# Transformer_FrontEnd_3.net
KiCad netlist of a schematic drawn in Altium Designer
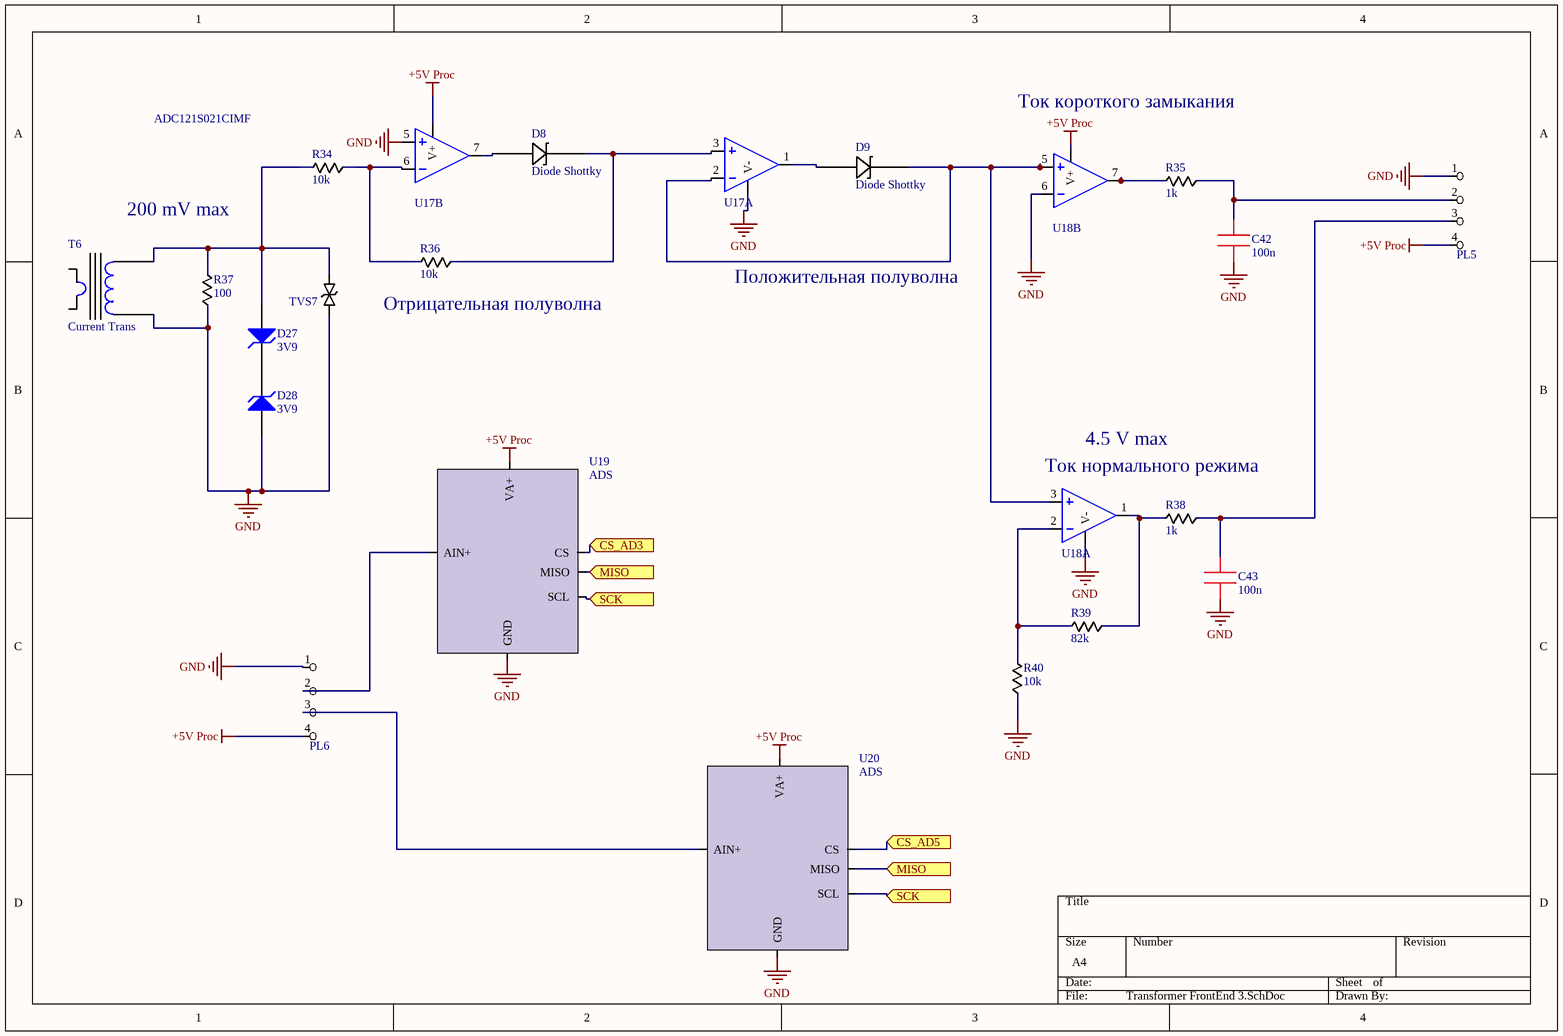
[diagram p0: Transformer FrontEnd 3.SchDoc]

(export (version "E")
  (design (tool "Eeschema 10.0.6"))
  (components
    (comp (ref "C42")
      (value "100n")
      (footprint "0603")
      (description "CC0603KRX7R9BB104")
      (libsource (lib "kontr") (part "0603 CAP"))
    )
    (comp (ref "C43")
      (value "100n")
      (footprint "0603")
      (description "CC0603KRX7R9BB104")
      (libsource (lib "kontr") (part "0603 CAP"))
    )
    (comp (ref "D8")
      (value "Diode Shottky")
      (footprint "SOD523")
      (description "RB751S40T1G")
      (libsource (lib "kontr") (part "Diode Shottky"))
    )
    (comp (ref "D9")
      (value "Diode Shottky")
      (footprint "SOD523")
      (description "RB751S40T1G")
      (libsource (lib "kontr") (part "Diode Shottky"))
    )
    (comp (ref "D27")
      (value "3V9")
      (footprint "PcbLib1:SOD80C")
      (description "BZV55-C3V9,115")
      (libsource (lib "Miscellaneous Devices") (part "D Zener"))
    )
    (comp (ref "D28")
      (value "3V9")
      (footprint "PcbLib1:SOD80C")
      (description "BZV55-C3V9,115")
      (libsource (lib "Miscellaneous Devices") (part "D Zener"))
    )
    (comp (ref "PL5")
      (value "plug")
      (footprint "PLS 4")
      (description "PLS-4R (DS1022-1x4R)")
      (libsource (lib "kontr") (part "PLS-4R"))
    )
    (comp (ref "PL6")
      (value "plug")
      (footprint "PLS 4")
      (description "PLS-4R (DS1022-1x4R)")
      (libsource (lib "kontr") (part "PLS-4R"))
    )
    (comp (ref "R34")
      (value "10k")
      (footprint "0603")
      (description "RT0603FRE0710KL")
      (libsource (lib "kontr") (part "0603 RES"))
    )
    (comp (ref "R35")
      (value "1k")
      (footprint "0603")
      (description "RC0603FR-071KL")
      (libsource (lib "kontr") (part "0603 RES"))
    )
    (comp (ref "R36")
      (value "10k")
      (footprint "0603")
      (description "RT0603FRE0710KL")
      (libsource (lib "kontr") (part "0603 RES"))
    )
    (comp (ref "R37")
      (value "100")
      (footprint "1206")
      (description "RT1206BRD07100RL")
      (libsource (lib "kontr") (part "SMD Resistor"))
    )
    (comp (ref "R38")
      (value "1k")
      (footprint "0603")
      (description "RC0603FR-071KL")
      (libsource (lib "kontr") (part "0603 RES"))
    )
    (comp (ref "R39")
      (value "82k")
      (footprint "0603")
      (description "ERJ3EKF8202V")
      (libsource (lib "kontr") (part "0603 RES"))
    )
    (comp (ref "R40")
      (value "10k")
      (footprint "0603")
      (description "RT0603FRE0710KL")
      (libsource (lib "kontr") (part "0603 RES"))
    )
    (comp (ref "T6")
      (value "Current Trans")
      (footprint "Talema")
      (description "AC-1005")
      (libsource (lib "kontr") (part "Current Trans"))
    )
    (comp (ref "TVS7")
      (value "SMAJ5.0CA")
      (footprint "DO-214AC")
      (libsource (lib "kontr") (part "SMAJ5.0CA"))
    )
    (comp (ref "U17")
      (value "OPAMP 2Ch")
      (footprint "SOIC 8")
      (description "TS272IDT")
      (libsource (lib "kontr") (part "OPAMP 2Ch"))
    )
    (comp (ref "U18")
      (value "OPAMP 2Ch")
      (footprint "SOIC 8")
      (description "TS272IDT")
      (libsource (lib "kontr") (part "OPAMP 2Ch"))
    )
    (comp (ref "U19")
      (value "ADS")
      (footprint "SOT23 - 6")
      (description "ADC121S021CIMF")
      (libsource (lib "kontr") (part "ADS"))
    )
    (comp (ref "U20")
      (value "ADS")
      (footprint "SOT23 - 6")
      (description "ADC121S021CIMF")
      (libsource (lib "kontr") (part "ADS"))
    )
  )
  (nets
    (net (code "1") (name "+5V Proc") (class "Default")
      (node (ref "PL5") (pin "4") (pinfunction "2_4") (pintype "passive"))
      (node (ref "PL6") (pin "4") (pinfunction "2_4") (pintype "passive"))
      (node (ref "U17") (pin "8") (pinfunction "V+_8") (pintype "passive"))
      (node (ref "U18") (pin "8") (pinfunction "V+_8") (pintype "passive"))
      (node (ref "U19") (pin "1") (pinfunction "VA+_1") (pintype "passive"))
      (node (ref "U20") (pin "1") (pinfunction "VA+_1") (pintype "passive"))
    )
    (net (code "2") (name "/CS_AD3") (class "Default")
      (node (ref "U19") (pin "6") (pinfunction "CS_6") (pintype "passive"))
    )
    (net (code "3") (name "/CS_AD5") (class "Default")
      (node (ref "U20") (pin "6") (pinfunction "CS_6") (pintype "passive"))
    )
    (net (code "4") (name "/MISO") (class "Default")
      (node (ref "U19") (pin "5") (pinfunction "MISO_5") (pintype "passive"))
      (node (ref "U20") (pin "5") (pinfunction "MISO_5") (pintype "passive"))
    )
    (net (code "5") (name "/SCK") (class "Default")
      (node (ref "U19") (pin "4") (pinfunction "SCL_4") (pintype "passive"))
      (node (ref "U20") (pin "4") (pinfunction "SCL_4") (pintype "passive"))
    )
    (net (code "6") (name "GND") (class "Default")
      (node (ref "C42") (pin "1") (pinfunction "1_1") (pintype "passive"))
      (node (ref "C43") (pin "1") (pinfunction "1_1") (pintype "passive"))
      (node (ref "D28") (pin "1") (pinfunction "A_1") (pintype "passive"))
      (node (ref "PL5") (pin "1") (pinfunction "1_1") (pintype "passive"))
      (node (ref "PL6") (pin "1") (pinfunction "1_1") (pintype "passive"))
      (node (ref "R37") (pin "1") (pintype "passive"))
      (node (ref "R40") (pin "1") (pintype "passive"))
      (node (ref "T6") (pin "2") (pinfunction "2_2") (pintype "passive"))
      (node (ref "TVS7") (pin "1") (pinfunction "1_1") (pintype "passive"))
      (node (ref "U17") (pin "4") (pinfunction "V-_4") (pintype "passive"))
      (node (ref "U17") (pin "5") (pinfunction "+IN_5") (pintype "passive"))
      (node (ref "U18") (pin "4") (pinfunction "V-_4") (pintype "passive"))
      (node (ref "U18") (pin "6") (pinfunction "-IN_6") (pintype "passive"))
      (node (ref "U19") (pin "2") (pinfunction "GND_2") (pintype "passive"))
      (node (ref "U20") (pin "2") (pinfunction "GND_2") (pintype "passive"))
    )
    (net (code "7") (name "Net-(C42-Pad2)") (class "Default")
      (node (ref "C42") (pin "2") (pinfunction "2_2") (pintype "passive"))
      (node (ref "PL5") (pin "2") (pinfunction "2_2") (pintype "passive"))
      (node (ref "R35") (pin "1") (pintype "passive"))
    )
    (net (code "8") (name "Net-(C43-Pad2)") (class "Default")
      (node (ref "C43") (pin "2") (pinfunction "2_2") (pintype "passive"))
      (node (ref "PL5") (pin "3") (pinfunction "1_3") (pintype "passive"))
      (node (ref "R38") (pin "1") (pintype "passive"))
    )
    (net (code "9") (name "Net-(D27-A)") (class "Default")
      (node (ref "D27") (pin "1") (pinfunction "A_1") (pintype "passive"))
      (node (ref "R34") (pin "2") (pintype "passive"))
      (node (ref "R37") (pin "2") (pintype "passive"))
      (node (ref "T6") (pin "1") (pinfunction "1_1") (pintype "passive"))
      (node (ref "TVS7") (pin "2") (pinfunction "2_2") (pintype "passive"))
    )
    (net (code "10") (name "Net-(D27-K)") (class "Default")
      (node (ref "D27") (pin "2") (pinfunction "K_2") (pintype "passive"))
      (node (ref "D28") (pin "2") (pinfunction "K_2") (pintype "passive"))
    )
    (net (code "11") (name "Net-(U17A-+IN)") (class "Default")
      (node (ref "D8") (pin "2") (pinfunction "2_2") (pintype "passive"))
      (node (ref "R36") (pin "1") (pintype "passive"))
      (node (ref "U17") (pin "3") (pinfunction "+IN_3") (pintype "passive"))
    )
    (net (code "12") (name "Net-(U17A--IN)") (class "Default")
      (node (ref "D9") (pin "2") (pinfunction "2_2") (pintype "passive"))
      (node (ref "U17") (pin "2") (pinfunction "-IN_2") (pintype "passive"))
      (node (ref "U18") (pin "3") (pinfunction "+IN_3") (pintype "passive"))
      (node (ref "U18") (pin "5") (pinfunction "+IN_5") (pintype "passive"))
    )
    (net (code "13") (name "Net-(U17A-OUT)") (class "Default")
      (node (ref "D9") (pin "1") (pinfunction "1_1") (pintype "passive"))
      (node (ref "U17") (pin "1") (pinfunction "OUT_1") (pintype "passive"))
    )
    (net (code "14") (name "Net-(U17B--IN)") (class "Default")
      (node (ref "R34") (pin "1") (pintype "passive"))
      (node (ref "R36") (pin "2") (pintype "passive"))
      (node (ref "U17") (pin "6") (pinfunction "-IN_6") (pintype "passive"))
    )
    (net (code "15") (name "Net-(U17B-OUT)") (class "Default")
      (node (ref "D8") (pin "1") (pinfunction "1_1") (pintype "passive"))
      (node (ref "U17") (pin "7") (pinfunction "OUT_7") (pintype "passive"))
    )
    (net (code "16") (name "Net-(U18A--IN)") (class "Default")
      (node (ref "R39") (pin "2") (pintype "passive"))
      (node (ref "R40") (pin "2") (pintype "passive"))
      (node (ref "U18") (pin "2") (pinfunction "-IN_2") (pintype "passive"))
    )
    (net (code "17") (name "Net-(U18A-OUT)") (class "Default")
      (node (ref "R38") (pin "2") (pintype "passive"))
      (node (ref "R39") (pin "1") (pintype "passive"))
      (node (ref "U18") (pin "1") (pinfunction "OUT_1") (pintype "passive"))
    )
    (net (code "18") (name "Net-(U18B-OUT)") (class "Default")
      (node (ref "R35") (pin "2") (pintype "passive"))
      (node (ref "U18") (pin "7") (pinfunction "OUT_7") (pintype "passive"))
    )
    (net (code "19") (name "Net-(U19-AIN+)") (class "Default")
      (node (ref "PL6") (pin "2") (pinfunction "2_2") (pintype "passive"))
      (node (ref "U19") (pin "3") (pinfunction "AIN+_3") (pintype "passive"))
    )
    (net (code "20") (name "Net-(U20-AIN+)") (class "Default")
      (node (ref "PL6") (pin "3") (pinfunction "1_3") (pintype "passive"))
      (node (ref "U20") (pin "3") (pinfunction "AIN+_3") (pintype "passive"))
    )
  )
)
